# SCH_Roomba_esp8266_12F_2022-09-12.net
KiCad netlist of a schematic drawn in EasyEDA
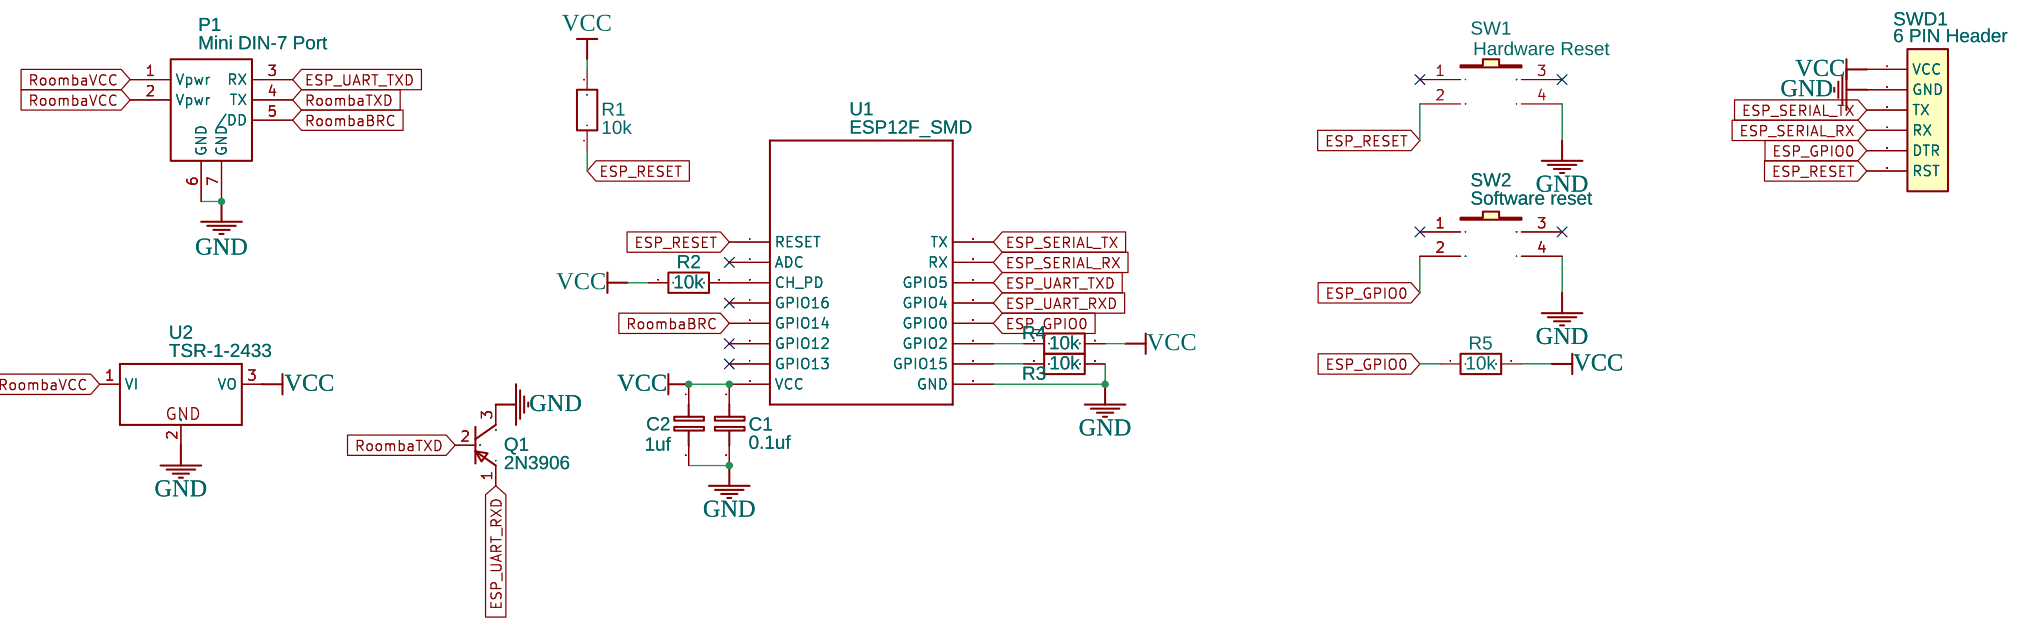
[diagram p0: schematic sheet]

(export (version "E")
  (design (tool "Eeschema 10.0.6"))
  (components
    (comp (ref "C1")
      (value "0.1uf")
      (fields (field (name "BOM_Manufacturer Part") "?"))
      (libsource (lib "") (part "Capacitor"))
    )
    (comp (ref "C2")
      (value "1uf")
      (fields (field (name "BOM_Manufacturer Part") "?"))
      (libsource (lib "") (part "Capacitor"))
    )
    (comp (ref "P1") (value "Mini DIN-7 Port") (libsource (lib "") (part "Mini DIN-7 Port")))
    (comp (ref "Q1")
      (value "2N3906")
      (fields (field (name "BOM_Supplier Part") "C9809"))
      (libsource (lib "") (part "2N3906"))
    )
    (comp (ref "R1") (value "10k") (libsource (lib "") (part "R_0603_EU_1")))
    (comp (ref "R2") (value "10k") (libsource (lib "") (part "R_0603_EU")))
    (comp (ref "R3") (value "10k") (libsource (lib "") (part "R_0603_EU")))
    (comp (ref "R4") (value "10k") (libsource (lib "") (part "R_0603_EU")))
    (comp (ref "R5") (value "10k") (libsource (lib "") (part "R_0603_EU")))
    (comp (ref "SW1")
      (value "Hardware Reset")
      (fields
        (field (name "BOM_Manufacturer Part") "SWITCH-6x6x5_TH")
        (field (name "BOM_Supplier Part") "E69330")
      )
      (libsource (lib "") (part "Unknown_775_40"))
    )
    (comp (ref "SW2")
      (value "Software reset")
      (fields
        (field (name "BOM_Manufacturer Part") "SWITCH-6x6x5_TH")
        (field (name "BOM_Supplier Part") "E69330")
      )
      (libsource (lib "") (part "Unknown_775_115"))
    )
    (comp (ref "SWD1")
      (value "6 PIN Header")
      (fields (field (name "BOM_Manufacturer Part") "New SchematicLib"))
      (libsource (lib "") (part "6 PIN Header"))
    )
    (comp (ref "U1")
      (value "ESP12F_SMD")
      (fields (field (name "BOM_Manufacturer Part") "?"))
      (libsource (lib "") (part "Unknown_475_155"))
    )
    (comp (ref "U2")
      (value "TSR-1-2433")
      (fields (field (name "BOM_Manufacturer Part") "?"))
      (libsource (lib "") (part "Unknown_135_195"))
    )
  )
  (nets
    (net (code "1") (name "ESP_GPIO0") (class "Default")
      (node (ref "R5") (pin "1") (pinfunction "1_1") (pintype "unspecified"))
      (node (ref "SW2") (pin "2") (pinfunction "2_2") (pintype "input"))
      (node (ref "SWD1") (pin "5") (pinfunction "DTR_5") (pintype "input"))
      (node (ref "U1") (pin "12") (pinfunction "GPIO0_12") (pintype "unspecified"))
    )
    (net (code "2") (name "ESP_RESET") (class "Default")
      (node (ref "R1") (pin "1") (pinfunction "1_1") (pintype "unspecified"))
      (node (ref "SW1") (pin "2") (pinfunction "2_2") (pintype "input"))
      (node (ref "SWD1") (pin "6") (pinfunction "RST_6") (pintype "input"))
      (node (ref "U1") (pin "1") (pinfunction "RESET_1") (pintype "unspecified"))
    )
    (net (code "3") (name "ESP_SERIAL_RX") (class "Default")
      (node (ref "SWD1") (pin "4") (pinfunction "RX_4") (pintype "input"))
      (node (ref "U1") (pin "15") (pinfunction "RX_15") (pintype "unspecified"))
    )
    (net (code "4") (name "ESP_SERIAL_TX") (class "Default")
      (node (ref "SWD1") (pin "3") (pinfunction "TX_3") (pintype "input"))
      (node (ref "U1") (pin "16") (pinfunction "TX_16") (pintype "unspecified"))
    )
    (net (code "5") (name "ESP_UART_RXD") (class "Default")
      (node (ref "Q1") (pin "1") (pinfunction "E_1") (pintype "unspecified"))
      (node (ref "U1") (pin "13") (pinfunction "GPIO4_13") (pintype "unspecified"))
    )
    (net (code "6") (name "ESP_UART_TXD") (class "Default")
      (node (ref "P1") (pin "3") (pinfunction "RX_3") (pintype "input"))
      (node (ref "U1") (pin "14") (pinfunction "GPIO5_14") (pintype "unspecified"))
    )
    (net (code "7") (name "GND") (class "Default")
      (node (ref "C1") (pin "2") (pinfunction "2_2") (pintype "unspecified"))
      (node (ref "C2") (pin "2") (pinfunction "2_2") (pintype "unspecified"))
      (node (ref "P1") (pin "6") (pinfunction "GND_6") (pintype "passive"))
      (node (ref "P1") (pin "7") (pinfunction "GND_7") (pintype "passive"))
      (node (ref "Q1") (pin "3") (pinfunction "C_3") (pintype "unspecified"))
      (node (ref "R3") (pin "2") (pinfunction "2_2") (pintype "unspecified"))
      (node (ref "SW1") (pin "4") (pinfunction "4_4") (pintype "input"))
      (node (ref "SW2") (pin "4") (pinfunction "4_4") (pintype "input"))
      (node (ref "SWD1") (pin "2") (pinfunction "GND_2") (pintype "input"))
      (node (ref "U1") (pin "9") (pinfunction "GND_9") (pintype "unspecified"))
      (node (ref "U2") (pin "2") (pinfunction "GND_2") (pintype "passive"))
    )
    (net (code "8") (name "Net-(U1-CH_PD)") (class "Default")
      (node (ref "R2") (pin "2") (pinfunction "2_2") (pintype "unspecified"))
      (node (ref "U1") (pin "3") (pinfunction "CH_PD_3") (pintype "unspecified"))
    )
    (net (code "9") (name "Net-(U1-GPIO2)") (class "Default")
      (node (ref "R4") (pin "1") (pinfunction "1_1") (pintype "unspecified"))
      (node (ref "U1") (pin "11") (pinfunction "GPIO2_11") (pintype "unspecified"))
    )
    (net (code "10") (name "Net-(U1-GPIO15)") (class "Default")
      (node (ref "R3") (pin "1") (pinfunction "1_1") (pintype "unspecified"))
      (node (ref "U1") (pin "10") (pinfunction "GPIO15_10") (pintype "unspecified"))
    )
    (net (code "11") (name "RoombaBRC") (class "Default")
      (node (ref "P1") (pin "5") (pinfunction "/DD_5") (pintype "input"))
      (node (ref "U1") (pin "5") (pinfunction "GPIO14_5") (pintype "unspecified"))
    )
    (net (code "12") (name "RoombaTXD") (class "Default")
      (node (ref "P1") (pin "4") (pinfunction "TX_4") (pintype "output"))
      (node (ref "Q1") (pin "2") (pinfunction "B_2") (pintype "unspecified"))
    )
    (net (code "13") (name "RoombaVCC") (class "Default")
      (node (ref "P1") (pin "1") (pinfunction "Vpwr_1") (pintype "unspecified"))
      (node (ref "P1") (pin "2") (pinfunction "Vpwr_2") (pintype "unspecified"))
      (node (ref "U2") (pin "1") (pinfunction "VI_1") (pintype "unspecified"))
    )
    (net (code "14") (name "VCC") (class "Default")
      (node (ref "C1") (pin "1") (pinfunction "1_1") (pintype "unspecified"))
      (node (ref "C2") (pin "1") (pinfunction "1_1") (pintype "unspecified"))
      (node (ref "R1") (pin "2") (pinfunction "2_2") (pintype "unspecified"))
      (node (ref "R2") (pin "1") (pinfunction "1_1") (pintype "unspecified"))
      (node (ref "R4") (pin "2") (pinfunction "2_2") (pintype "unspecified"))
      (node (ref "R5") (pin "2") (pinfunction "2_2") (pintype "unspecified"))
      (node (ref "SWD1") (pin "1") (pinfunction "VCC_1") (pintype "input"))
      (node (ref "U1") (pin "8") (pinfunction "VCC_8") (pintype "unspecified"))
      (node (ref "U2") (pin "3") (pinfunction "VO_3") (pintype "passive"))
    )
    (net (code "15") (name "unconnected-(SW1-Pad1)") (class "Default")
      (node (ref "SW1") (pin "1") (pinfunction "1_1") (pintype "input+no_connect"))
    )
    (net (code "16") (name "unconnected-(SW1-Pad3)") (class "Default")
      (node (ref "SW1") (pin "3") (pinfunction "3_3") (pintype "input+no_connect"))
    )
    (net (code "17") (name "unconnected-(SW2-Pad1)") (class "Default")
      (node (ref "SW2") (pin "1") (pinfunction "1_1") (pintype "input+no_connect"))
    )
    (net (code "18") (name "unconnected-(SW2-Pad3)") (class "Default")
      (node (ref "SW2") (pin "3") (pinfunction "3_3") (pintype "input+no_connect"))
    )
    (net (code "19") (name "unconnected-(U1-ADC-Pad2)") (class "Default")
      (node (ref "U1") (pin "2") (pinfunction "ADC_2") (pintype "unspecified+no_connect"))
    )
    (net (code "20") (name "unconnected-(U1-GPIO12-Pad6)") (class "Default")
      (node (ref "U1") (pin "6") (pinfunction "GPIO12_6") (pintype "unspecified+no_connect"))
    )
    (net (code "21") (name "unconnected-(U1-GPIO13-Pad7)") (class "Default")
      (node (ref "U1") (pin "7") (pinfunction "GPIO13_7") (pintype "unspecified+no_connect"))
    )
    (net (code "22") (name "unconnected-(U1-GPIO16-Pad4)") (class "Default")
      (node (ref "U1") (pin "4") (pinfunction "GPIO16_4") (pintype "unspecified+no_connect"))
    )
  )
)
